# MXRDist.net
KiCad netlist of a schematic drawn in EAGLE
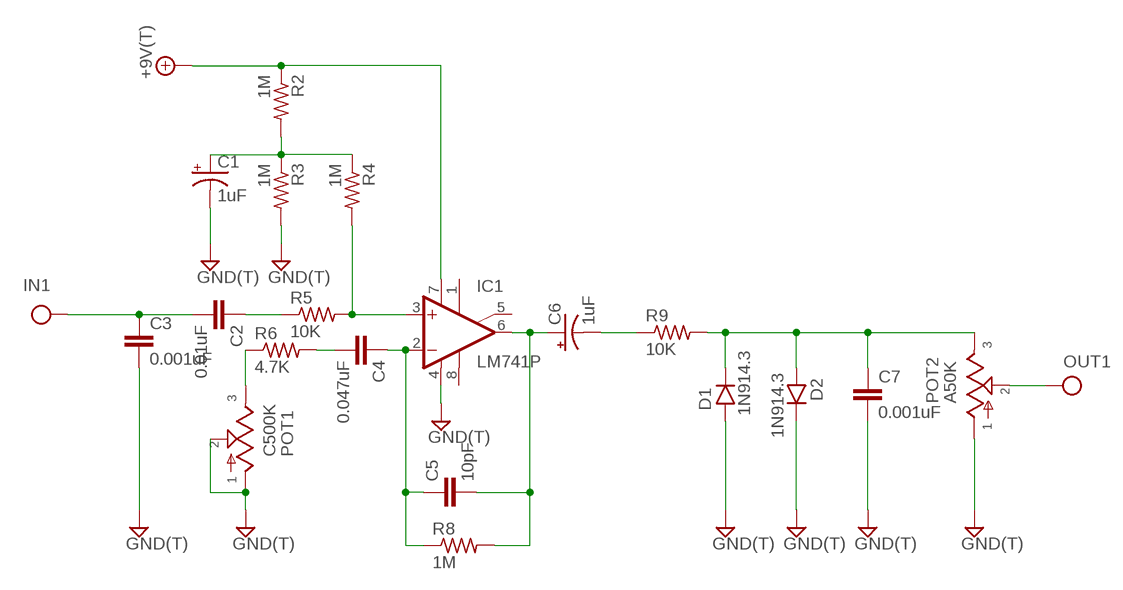
[diagram p0: schematic, sheet 1]

(export (version "E")
  (design (tool "Eeschema 10.0.6"))
  (components
    (comp (ref "+9V1")
      (value "+9V(T)")
      (footprint "eagle-import:SQUARE")
      (libsource (lib "eagle-import") (part "+9V(T)"))
    )
    (comp (ref "C1")
      (value "1uF")
      (footprint "eagle-import:044A")
      (libsource (lib "eagle-import") (part "044A1"))
    )
    (comp (ref "C2")
      (value "0.01uF")
      (footprint "eagle-import:070X030")
      (libsource (lib "eagle-import") (part "070X0302"))
    )
    (comp (ref "C3")
      (value "0.001uF")
      (footprint "eagle-import:070X030")
      (libsource (lib "eagle-import") (part "070X0302"))
    )
    (comp (ref "C4")
      (value "0.047uF")
      (footprint "eagle-import:075X040")
      (libsource (lib "eagle-import") (part "075X0402"))
    )
    (comp (ref "C5")
      (value "10pF")
      (footprint "eagle-import:050X030_025")
      (libsource (lib "eagle-import") (part "050X030_0251"))
    )
    (comp (ref "C6")
      (value "1uF")
      (footprint "eagle-import:044A")
      (libsource (lib "eagle-import") (part "044A1"))
    )
    (comp (ref "C7")
      (value "0.001uF")
      (footprint "eagle-import:070X030")
      (libsource (lib "eagle-import") (part "070X0302"))
    )
    (comp (ref "D1")
      (value "1N914.3")
      (footprint "eagle-import:DO35-3")
      (libsource (lib "eagle-import") (part "1N914.3"))
    )
    (comp (ref "D2")
      (value "1N914.3")
      (footprint "eagle-import:DO35-3")
      (libsource (lib "eagle-import") (part "1N914.3"))
    )
    (comp (ref "GND1")
      (value "GND(T)")
      (footprint "eagle-import:SQUARE")
      (libsource (lib "eagle-import") (part "GND(T)"))
    )
    (comp (ref "GND2")
      (value "GND(T)")
      (footprint "eagle-import:SQUARE")
      (libsource (lib "eagle-import") (part "GND(T)"))
    )
    (comp (ref "GND3")
      (value "GND(T)")
      (footprint "eagle-import:SQUARE")
      (libsource (lib "eagle-import") (part "GND(T)"))
    )
    (comp (ref "GND4")
      (value "GND(T)")
      (footprint "eagle-import:SQUARE")
      (libsource (lib "eagle-import") (part "GND(T)"))
    )
    (comp (ref "GND5")
      (value "GND(T)")
      (footprint "eagle-import:SQUARE")
      (libsource (lib "eagle-import") (part "GND(T)"))
    )
    (comp (ref "GND6")
      (value "GND(T)")
      (footprint "eagle-import:SQUARE")
      (libsource (lib "eagle-import") (part "GND(T)"))
    )
    (comp (ref "GND7")
      (value "GND(T)")
      (footprint "eagle-import:SQUARE")
      (libsource (lib "eagle-import") (part "GND(T)"))
    )
    (comp (ref "GND8")
      (value "GND(T)")
      (footprint "eagle-import:SQUARE")
      (libsource (lib "eagle-import") (part "GND(T)"))
    )
    (comp (ref "GND9")
      (value "GND(T)")
      (footprint "eagle-import:SQUARE")
      (libsource (lib "eagle-import") (part "GND(T)"))
    )
    (comp (ref "IC1")
      (value "LM741P")
      (footprint "eagle-import:DIL08")
      (libsource (lib "eagle-import") (part "741PLM"))
    )
    (comp (ref "IN1")
      (value "IN(T)")
      (footprint "eagle-import:SQUARE")
      (libsource (lib "eagle-import") (part "IN(T)"))
    )
    (comp (ref "OUT1")
      (value "OUT(T)")
      (footprint "eagle-import:SQUARE")
      (libsource (lib "eagle-import") (part "OUT(T)"))
    )
    (comp (ref "POT1")
      (value "C500K")
      (footprint "eagle-import:16MM")
      (libsource (lib "eagle-import") (part "POT16MM"))
    )
    (comp (ref "POT2")
      (value "A50K")
      (footprint "eagle-import:16MM")
      (libsource (lib "eagle-import") (part "POT16MM"))
    )
    (comp (ref "R2")
      (value "1M")
      (footprint "eagle-import:R0207_3")
      (libsource (lib "eagle-import") (part "6MM.3"))
    )
    (comp (ref "R3")
      (value "1M")
      (footprint "eagle-import:R0207_3")
      (libsource (lib "eagle-import") (part "6MM.3"))
    )
    (comp (ref "R4")
      (value "1M")
      (footprint "eagle-import:R0207_3")
      (libsource (lib "eagle-import") (part "6MM.3"))
    )
    (comp (ref "R5")
      (value "10K")
      (footprint "eagle-import:R0207_3")
      (libsource (lib "eagle-import") (part "6MM.3"))
    )
    (comp (ref "R6")
      (value "4.7K")
      (footprint "eagle-import:R0207_3")
      (libsource (lib "eagle-import") (part "6MM.3"))
    )
    (comp (ref "R8")
      (value "1M")
      (footprint "eagle-import:R0207_3")
      (libsource (lib "eagle-import") (part "6MM.3"))
    )
    (comp (ref "R9")
      (value "10K")
      (footprint "eagle-import:R0207_3")
      (libsource (lib "eagle-import") (part "6MM.3"))
    )
  )
  (nets
    (net (code "1") (name "+9V(T)") (class "Default")
      (node (ref "+9V1") (pin "1") (pinfunction "+9V_1") (pintype "power_in"))
      (node (ref "IC1") (pin "7") (pinfunction "V+_7") (pintype "power_in"))
      (node (ref "R2") (pin "1") (pinfunction "1_1") (pintype "passive"))
    )
    (net (code "2") (name "GND(T)") (class "Default")
      (node (ref "C1") (pin "2") (pinfunction "-_2") (pintype "passive"))
      (node (ref "C3") (pin "2") (pinfunction "2_2") (pintype "passive"))
      (node (ref "C7") (pin "2") (pinfunction "2_2") (pintype "passive"))
      (node (ref "D1") (pin "A") (pinfunction "A_A") (pintype "passive"))
      (node (ref "D2") (pin "C") (pinfunction "C_C") (pintype "passive"))
      (node (ref "GND1") (pin "1") (pinfunction "GND_1") (pintype "power_in"))
      (node (ref "GND2") (pin "1") (pinfunction "GND_1") (pintype "power_in"))
      (node (ref "GND3") (pin "1") (pinfunction "GND_1") (pintype "power_in"))
      (node (ref "GND4") (pin "1") (pinfunction "GND_1") (pintype "power_in"))
      (node (ref "GND5") (pin "1") (pinfunction "GND_1") (pintype "power_in"))
      (node (ref "GND6") (pin "1") (pinfunction "GND_1") (pintype "power_in"))
      (node (ref "GND7") (pin "1") (pinfunction "GND_1") (pintype "power_in"))
      (node (ref "GND8") (pin "1") (pinfunction "GND_1") (pintype "power_in"))
      (node (ref "GND9") (pin "1") (pinfunction "GND_1") (pintype "power_in"))
      (node (ref "IC1") (pin "4") (pinfunction "V-_4") (pintype "power_in"))
      (node (ref "POT1") (pin "1") (pinfunction "1_1") (pintype "passive"))
      (node (ref "POT1") (pin "2") (pinfunction "2_2") (pintype "passive"))
      (node (ref "POT2") (pin "1") (pinfunction "1_1") (pintype "passive"))
      (node (ref "R3") (pin "2") (pinfunction "2_2") (pintype "passive"))
    )
    (net (code "3") (name "IN(T)") (class "Default")
      (node (ref "C2") (pin "2") (pinfunction "2_2") (pintype "passive"))
      (node (ref "C3") (pin "1") (pinfunction "1_1") (pintype "passive"))
      (node (ref "IN1") (pin "1") (pinfunction "IN_1") (pintype "power_in"))
    )
    (net (code "4") (name "Net-(C1-+)") (class "Default")
      (node (ref "C1") (pin "1") (pinfunction "+_1") (pintype "passive"))
      (node (ref "R2") (pin "2") (pinfunction "2_2") (pintype "passive"))
      (node (ref "R3") (pin "1") (pinfunction "1_1") (pintype "passive"))
      (node (ref "R4") (pin "1") (pinfunction "1_1") (pintype "passive"))
    )
    (net (code "5") (name "Net-(C2-Pad1)") (class "Default")
      (node (ref "C2") (pin "1") (pinfunction "1_1") (pintype "passive"))
      (node (ref "R5") (pin "1") (pinfunction "1_1") (pintype "passive"))
    )
    (net (code "6") (name "Net-(C4-Pad2)") (class "Default")
      (node (ref "C4") (pin "2") (pinfunction "2_2") (pintype "passive"))
      (node (ref "R6") (pin "2") (pinfunction "2_2") (pintype "passive"))
    )
    (net (code "7") (name "Net-(C6-+)") (class "Default")
      (node (ref "C5") (pin "2") (pinfunction "2_2") (pintype "passive"))
      (node (ref "C6") (pin "1") (pinfunction "+_1") (pintype "passive"))
      (node (ref "IC1") (pin "6") (pinfunction "OUT_6") (pintype "output"))
      (node (ref "R8") (pin "2") (pinfunction "2_2") (pintype "passive"))
    )
    (net (code "8") (name "Net-(C6--)") (class "Default")
      (node (ref "C6") (pin "2") (pinfunction "-_2") (pintype "passive"))
      (node (ref "R9") (pin "1") (pinfunction "1_1") (pintype "passive"))
    )
    (net (code "9") (name "Net-(C7-Pad1)") (class "Default")
      (node (ref "C7") (pin "1") (pinfunction "1_1") (pintype "passive"))
      (node (ref "D1") (pin "C") (pinfunction "C_C") (pintype "passive"))
      (node (ref "D2") (pin "A") (pinfunction "A_A") (pintype "passive"))
      (node (ref "POT2") (pin "3") (pinfunction "3_3") (pintype "passive"))
      (node (ref "R9") (pin "2") (pinfunction "2_2") (pintype "passive"))
    )
    (net (code "10") (name "Net-(IC1-+IN)") (class "Default")
      (node (ref "IC1") (pin "3") (pinfunction "+IN_3") (pintype "input"))
      (node (ref "R4") (pin "2") (pinfunction "2_2") (pintype "passive"))
      (node (ref "R5") (pin "2") (pinfunction "2_2") (pintype "passive"))
    )
    (net (code "11") (name "Net-(IC1--IN)") (class "Default")
      (node (ref "C4") (pin "1") (pinfunction "1_1") (pintype "passive"))
      (node (ref "C5") (pin "1") (pinfunction "1_1") (pintype "passive"))
      (node (ref "IC1") (pin "2") (pinfunction "-IN_2") (pintype "input"))
      (node (ref "R8") (pin "1") (pinfunction "1_1") (pintype "passive"))
    )
    (net (code "12") (name "Net-(POT1-Pad3)") (class "Default")
      (node (ref "POT1") (pin "3") (pinfunction "3_3") (pintype "passive"))
      (node (ref "R6") (pin "1") (pinfunction "1_1") (pintype "passive"))
    )
    (net (code "13") (name "OUT(T)") (class "Default")
      (node (ref "OUT1") (pin "1") (pinfunction "OUT_1") (pintype "power_in"))
      (node (ref "POT2") (pin "2") (pinfunction "2_2") (pintype "passive"))
    )
    (net (code "14") (name "unconnected-(IC1-ON1-Pad1)") (class "Default")
      (node (ref "IC1") (pin "1") (pinfunction "ON1_1") (pintype "passive"))
    )
    (net (code "15") (name "unconnected-(IC1-ON2-Pad5)") (class "Default")
      (node (ref "IC1") (pin "5") (pinfunction "ON2_5") (pintype "passive"))
    )
    (net (code "16") (name "unconnected-(IC1-OPT-Pad8)") (class "Default")
      (node (ref "IC1") (pin "8") (pinfunction "OPT_8") (pintype "passive"))
    )
  )
)
